# stx_v2.net
KiCad netlist of a schematic drawn in EAGLE
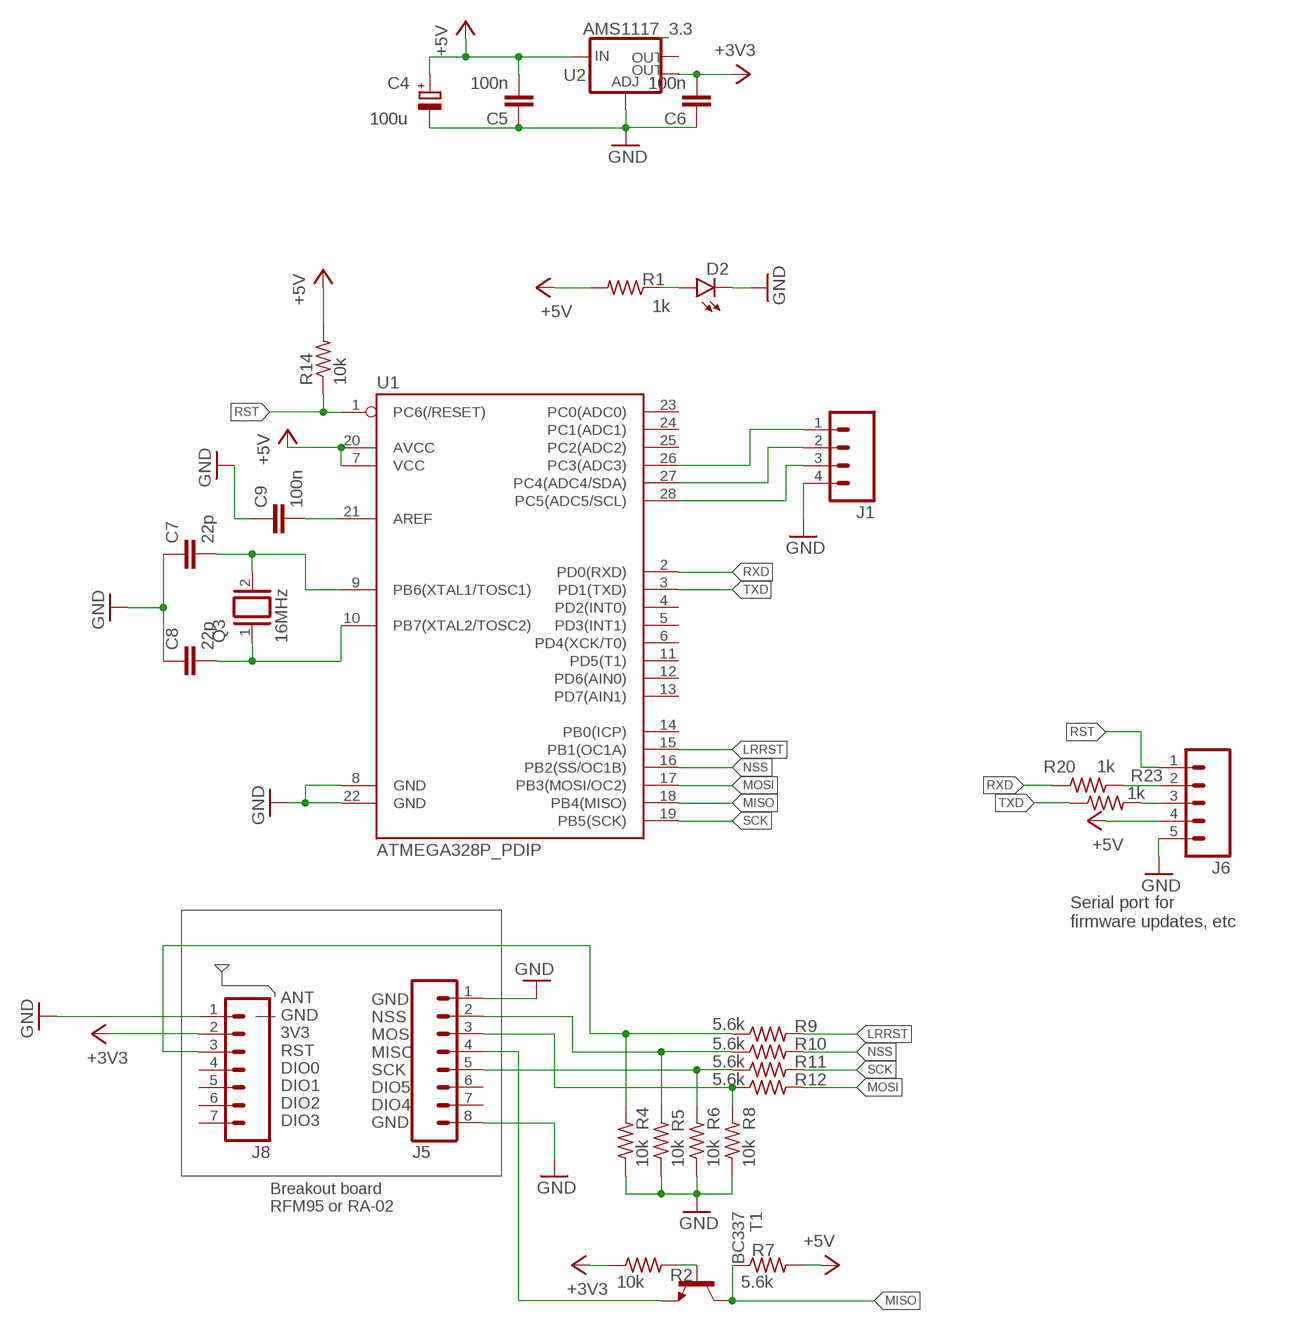
[diagram p0: schematic, sheet 1]

(export (version "E")
  (design (tool "Eeschema 10.0.6"))
  (components
    (comp (ref "C4")
      (value "100u")
      (footprint "eagle-import:E2,5-6E")
      (libsource (lib "eagle-import") (part "CPOL-EUE2,5-6E"))
    )
    (comp (ref "C5")
      (value "100n")
      (footprint "eagle-import:C050-024X044")
      (libsource (lib "eagle-import") (part "C-EU050-024X044"))
    )
    (comp (ref "C6")
      (value "100n")
      (footprint "eagle-import:C050-024X044")
      (libsource (lib "eagle-import") (part "C-EU050-024X044"))
    )
    (comp (ref "C7")
      (value "22p")
      (footprint "eagle-import:C050-024X044")
      (libsource (lib "eagle-import") (part "C-EU050-024X044"))
    )
    (comp (ref "C8")
      (value "22p")
      (footprint "eagle-import:C050-024X044")
      (libsource (lib "eagle-import") (part "C-EU050-024X044"))
    )
    (comp (ref "C9")
      (value "100n")
      (footprint "eagle-import:C050-024X044")
      (libsource (lib "eagle-import") (part "C-EU050-024X044"))
    )
    (comp (ref "D2")
      (value "LED3MM")
      (footprint "eagle-import:LED3MM")
      (libsource (lib "eagle-import") (part "LED3MM"))
    )
    (comp (ref "J1")
      (value "M04PTH")
      (footprint "eagle-import:1X04")
      (libsource (lib "eagle-import") (part "M04PTH"))
    )
    (comp (ref "J5")
      (value "M08")
      (footprint "eagle-import:1X08_ROUND")
      (libsource (lib "eagle-import") (part "M08"))
    )
    (comp (ref "J6")
      (value "M05PTH")
      (footprint "eagle-import:1X05")
      (libsource (lib "eagle-import") (part "M05PTH"))
    )
    (comp (ref "J8")
      (value "M07")
      (footprint "eagle-import:1X07")
      (libsource (lib "eagle-import") (part "M07"))
    )
    (comp (ref "Q3")
      (value "16MHz")
      (footprint "eagle-import:QS")
      (libsource (lib "eagle-import") (part "XTAL/S"))
    )
    (comp (ref "R1")
      (value "1k")
      (footprint "eagle-import:0204V")
      (libsource (lib "eagle-import") (part "R-US_0204/2V"))
    )
    (comp (ref "R2")
      (value "10k")
      (footprint "eagle-import:0204_7")
      (libsource (lib "eagle-import") (part "R-US_0204/7"))
    )
    (comp (ref "R4")
      (value "10k")
      (footprint "eagle-import:0204V")
      (libsource (lib "eagle-import") (part "R-US_0204/2V"))
    )
    (comp (ref "R5")
      (value "10k")
      (footprint "eagle-import:0204V")
      (libsource (lib "eagle-import") (part "R-US_0204/2V"))
    )
    (comp (ref "R6")
      (value "10k")
      (footprint "eagle-import:0204V")
      (libsource (lib "eagle-import") (part "R-US_0204/2V"))
    )
    (comp (ref "R7")
      (value "5.6k")
      (footprint "eagle-import:0204V")
      (libsource (lib "eagle-import") (part "R-US_0204/2V"))
    )
    (comp (ref "R8")
      (value "10k")
      (footprint "eagle-import:0204V")
      (libsource (lib "eagle-import") (part "R-US_0204/2V"))
    )
    (comp (ref "R9")
      (value "5.6k")
      (footprint "eagle-import:0204V")
      (libsource (lib "eagle-import") (part "R-US_0204/2V"))
    )
    (comp (ref "R10")
      (value "5.6k")
      (footprint "eagle-import:0204V")
      (libsource (lib "eagle-import") (part "R-US_0204/2V"))
    )
    (comp (ref "R11")
      (value "5.6k")
      (footprint "eagle-import:0204V")
      (libsource (lib "eagle-import") (part "R-US_0204/2V"))
    )
    (comp (ref "R12")
      (value "5.6k")
      (footprint "eagle-import:0204V")
      (libsource (lib "eagle-import") (part "R-US_0204/2V"))
    )
    (comp (ref "R14")
      (value "10k")
      (footprint "eagle-import:0204_7")
      (libsource (lib "eagle-import") (part "R-US_0204/7"))
    )
    (comp (ref "R20")
      (value "1k")
      (footprint "eagle-import:0204_7")
      (libsource (lib "eagle-import") (part "R-US_0204/7"))
    )
    (comp (ref "R23")
      (value "1k")
      (footprint "eagle-import:0204_7")
      (libsource (lib "eagle-import") (part "R-US_0204/7"))
    )
    (comp (ref "T1")
      (value "BC337")
      (footprint "eagle-import:TO92")
      (libsource (lib "eagle-import") (part "BC337"))
    )
    (comp (ref "U1")
      (value "ATMEGA328P_PDIP")
      (footprint "eagle-import:DIL28-3")
      (libsource (lib "eagle-import") (part "ATMEGA328P_PDIP"))
    )
    (comp (ref "U2")
      (value "AMS1117_3.3")
      (footprint "eagle-import:SOT223")
      (libsource (lib "eagle-import") (part "V_REG_LM1117SOT223"))
    )
  )
  (nets
    (net (code "1") (name "+3V3") (class "Default")
      (node (ref "C6") (pin "2") (pinfunction "2_2") (pintype "passive"))
      (node (ref "J8") (pin "2") (pinfunction "2_2") (pintype "passive"))
      (node (ref "R2") (pin "1") (pinfunction "1_1") (pintype "passive"))
      (node (ref "U2") (pin "4") (pinfunction "OUT_4") (pintype "output"))
    )
    (net (code "2") (name "+5V") (class "Default")
      (node (ref "C4") (pin "+") (pinfunction "+_+") (pintype "passive"))
      (node (ref "C5") (pin "2") (pinfunction "2_2") (pintype "passive"))
      (node (ref "J6") (pin "4") (pinfunction "4_4") (pintype "passive"))
      (node (ref "R1") (pin "2") (pinfunction "2_2") (pintype "passive"))
      (node (ref "R14") (pin "2") (pinfunction "2_2") (pintype "passive"))
      (node (ref "R7") (pin "2") (pinfunction "2_2") (pintype "passive"))
      (node (ref "U1") (pin "20") (pinfunction "AVCC_20") (pintype "bidirectional"))
      (node (ref "U1") (pin "7") (pinfunction "VCC_7") (pintype "bidirectional"))
      (node (ref "U2") (pin "3") (pinfunction "IN_3") (pintype "input"))
    )
    (net (code "3") (name "GND") (class "Default")
      (node (ref "C4") (pin "-") (pinfunction "-_-") (pintype "passive"))
      (node (ref "C5") (pin "1") (pinfunction "1_1") (pintype "passive"))
      (node (ref "C6") (pin "1") (pinfunction "1_1") (pintype "passive"))
      (node (ref "C7") (pin "1") (pinfunction "1_1") (pintype "passive"))
      (node (ref "C8") (pin "1") (pinfunction "1_1") (pintype "passive"))
      (node (ref "C9") (pin "1") (pinfunction "1_1") (pintype "passive"))
      (node (ref "D2") (pin "K") (pinfunction "C_K") (pintype "passive"))
      (node (ref "J1") (pin "4") (pinfunction "4_4") (pintype "passive"))
      (node (ref "J5") (pin "1") (pinfunction "1_1") (pintype "passive"))
      (node (ref "J5") (pin "8") (pinfunction "8_8") (pintype "passive"))
      (node (ref "J6") (pin "5") (pinfunction "5_5") (pintype "passive"))
      (node (ref "J8") (pin "1") (pinfunction "1_1") (pintype "passive"))
      (node (ref "R4") (pin "1") (pinfunction "1_1") (pintype "passive"))
      (node (ref "R5") (pin "1") (pinfunction "1_1") (pintype "passive"))
      (node (ref "R6") (pin "1") (pinfunction "1_1") (pintype "passive"))
      (node (ref "R8") (pin "1") (pinfunction "1_1") (pintype "passive"))
      (node (ref "U1") (pin "22") (pinfunction "GND_22") (pintype "bidirectional"))
      (node (ref "U1") (pin "8") (pinfunction "GND_8") (pintype "bidirectional"))
      (node (ref "U2") (pin "1") (pinfunction "ADJ_1") (pintype "input"))
    )
    (net (code "4") (name "LRRST") (class "Default")
      (node (ref "R9") (pin "2") (pinfunction "2_2") (pintype "passive"))
      (node (ref "U1") (pin "15") (pinfunction "PB1(OC1A)_15") (pintype "bidirectional"))
    )
    (net (code "5") (name "MISO") (class "Default")
      (node (ref "R7") (pin "1") (pinfunction "1_1") (pintype "passive"))
      (node (ref "T1") (pin "3") (pinfunction "C_3") (pintype "passive"))
      (node (ref "U1") (pin "18") (pinfunction "PB4(MISO)_18") (pintype "bidirectional"))
    )
    (net (code "6") (name "MOSI") (class "Default")
      (node (ref "R12") (pin "2") (pinfunction "2_2") (pintype "passive"))
      (node (ref "U1") (pin "17") (pinfunction "PB3(MOSI/OC2)_17") (pintype "bidirectional"))
    )
    (net (code "7") (name "NSS") (class "Default")
      (node (ref "R10") (pin "2") (pinfunction "2_2") (pintype "passive"))
      (node (ref "U1") (pin "16") (pinfunction "PB2(SS/OC1B)_16") (pintype "bidirectional"))
    )
    (net (code "8") (name "Net-(D2-PadA)") (class "Default")
      (node (ref "D2") (pin "A") (pinfunction "A_A") (pintype "passive"))
      (node (ref "R1") (pin "1") (pinfunction "1_1") (pintype "passive"))
    )
    (net (code "9") (name "Net-(J5-Pad2)") (class "Default")
      (node (ref "J5") (pin "2") (pinfunction "2_2") (pintype "passive"))
      (node (ref "R10") (pin "1") (pinfunction "1_1") (pintype "passive"))
      (node (ref "R5") (pin "2") (pinfunction "2_2") (pintype "passive"))
    )
    (net (code "10") (name "Net-(J5-Pad3)") (class "Default")
      (node (ref "J5") (pin "3") (pinfunction "3_3") (pintype "passive"))
      (node (ref "R12") (pin "1") (pinfunction "1_1") (pintype "passive"))
      (node (ref "R8") (pin "2") (pinfunction "2_2") (pintype "passive"))
    )
    (net (code "11") (name "Net-(J5-Pad5)") (class "Default")
      (node (ref "J5") (pin "5") (pinfunction "5_5") (pintype "passive"))
      (node (ref "R11") (pin "1") (pinfunction "1_1") (pintype "passive"))
      (node (ref "R6") (pin "2") (pinfunction "2_2") (pintype "passive"))
    )
    (net (code "12") (name "Net-(J6-Pad2)") (class "Default")
      (node (ref "J6") (pin "2") (pinfunction "2_2") (pintype "passive"))
      (node (ref "R20") (pin "2") (pinfunction "2_2") (pintype "passive"))
    )
    (net (code "13") (name "Net-(J6-Pad3)") (class "Default")
      (node (ref "J6") (pin "3") (pinfunction "3_3") (pintype "passive"))
      (node (ref "R23") (pin "2") (pinfunction "2_2") (pintype "passive"))
    )
    (net (code "14") (name "Net-(J8-Pad3)") (class "Default")
      (node (ref "J8") (pin "3") (pinfunction "3_3") (pintype "passive"))
      (node (ref "R4") (pin "2") (pinfunction "2_2") (pintype "passive"))
      (node (ref "R9") (pin "1") (pinfunction "1_1") (pintype "passive"))
    )
    (net (code "15") (name "Net-(T1-B)") (class "Default")
      (node (ref "R2") (pin "2") (pinfunction "2_2") (pintype "passive"))
      (node (ref "T1") (pin "2") (pinfunction "B_2") (pintype "passive"))
    )
    (net (code "16") (name "Net-(T1-E)") (class "Default")
      (node (ref "J5") (pin "4") (pinfunction "4_4") (pintype "passive"))
      (node (ref "T1") (pin "1") (pinfunction "E_1") (pintype "passive"))
    )
    (net (code "17") (name "Net-(U1-AREF)") (class "Default")
      (node (ref "C9") (pin "2") (pinfunction "2_2") (pintype "passive"))
      (node (ref "U1") (pin "21") (pinfunction "AREF_21") (pintype "bidirectional"))
    )
    (net (code "18") (name "Net-(U1-PB6(XTAL1{slash}TOSC1))") (class "Default")
      (node (ref "C7") (pin "2") (pinfunction "2_2") (pintype "passive"))
      (node (ref "Q3") (pin "2") (pinfunction "2_2") (pintype "passive"))
      (node (ref "U1") (pin "9") (pinfunction "PB6(XTAL1/TOSC1)_9") (pintype "bidirectional"))
    )
    (net (code "19") (name "Net-(U1-PB7(XTAL2{slash}TOSC2))") (class "Default")
      (node (ref "C8") (pin "2") (pinfunction "2_2") (pintype "passive"))
      (node (ref "Q3") (pin "1") (pinfunction "1_1") (pintype "passive"))
      (node (ref "U1") (pin "10") (pinfunction "PB7(XTAL2/TOSC2)_10") (pintype "bidirectional"))
    )
    (net (code "20") (name "Net-(U1-PC3(ADC3))") (class "Default")
      (node (ref "J1") (pin "1") (pinfunction "1_1") (pintype "passive"))
      (node (ref "U1") (pin "26") (pinfunction "PC3(ADC3)_26") (pintype "bidirectional"))
    )
    (net (code "21") (name "Net-(U1-PC4(ADC4{slash}SDA))") (class "Default")
      (node (ref "J1") (pin "2") (pinfunction "2_2") (pintype "passive"))
      (node (ref "U1") (pin "27") (pinfunction "PC4(ADC4/SDA)_27") (pintype "bidirectional"))
    )
    (net (code "22") (name "Net-(U1-PC5(ADC5{slash}SCL))") (class "Default")
      (node (ref "J1") (pin "3") (pinfunction "3_3") (pintype "passive"))
      (node (ref "U1") (pin "28") (pinfunction "PC5(ADC5/SCL)_28") (pintype "bidirectional"))
    )
    (net (code "23") (name "RST") (class "Default")
      (node (ref "J6") (pin "1") (pinfunction "1_1") (pintype "passive"))
      (node (ref "R14") (pin "1") (pinfunction "1_1") (pintype "passive"))
      (node (ref "U1") (pin "1") (pinfunction "PC6(/RESET)_1") (pintype "bidirectional"))
    )
    (net (code "24") (name "RXD") (class "Default")
      (node (ref "R20") (pin "1") (pinfunction "1_1") (pintype "passive"))
      (node (ref "U1") (pin "2") (pinfunction "PD0(RXD)_2") (pintype "bidirectional"))
    )
    (net (code "25") (name "SCK") (class "Default")
      (node (ref "R11") (pin "2") (pinfunction "2_2") (pintype "passive"))
      (node (ref "U1") (pin "19") (pinfunction "PB5(SCK)_19") (pintype "bidirectional"))
    )
    (net (code "26") (name "TXD") (class "Default")
      (node (ref "R23") (pin "1") (pinfunction "1_1") (pintype "passive"))
      (node (ref "U1") (pin "3") (pinfunction "PD1(TXD)_3") (pintype "bidirectional"))
    )
    (net (code "27") (name "unconnected-(J5-Pad6)") (class "Default")
      (node (ref "J5") (pin "6") (pinfunction "6_6") (pintype "passive"))
    )
    (net (code "28") (name "unconnected-(J5-Pad7)") (class "Default")
      (node (ref "J5") (pin "7") (pinfunction "7_7") (pintype "passive"))
    )
    (net (code "29") (name "unconnected-(J8-Pad4)") (class "Default")
      (node (ref "J8") (pin "4") (pinfunction "4_4") (pintype "passive"))
    )
    (net (code "30") (name "unconnected-(J8-Pad5)") (class "Default")
      (node (ref "J8") (pin "5") (pinfunction "5_5") (pintype "passive"))
    )
    (net (code "31") (name "unconnected-(J8-Pad6)") (class "Default")
      (node (ref "J8") (pin "6") (pinfunction "6_6") (pintype "passive"))
    )
    (net (code "32") (name "unconnected-(J8-Pad7)") (class "Default")
      (node (ref "J8") (pin "7") (pinfunction "7_7") (pintype "passive"))
    )
    (net (code "33") (name "unconnected-(U1-PB0(ICP)-Pad14)") (class "Default")
      (node (ref "U1") (pin "14") (pinfunction "PB0(ICP)_14") (pintype "bidirectional"))
    )
    (net (code "34") (name "unconnected-(U1-PC0(ADC0)-Pad23)") (class "Default")
      (node (ref "U1") (pin "23") (pinfunction "PC0(ADC0)_23") (pintype "bidirectional"))
    )
    (net (code "35") (name "unconnected-(U1-PC1(ADC1)-Pad24)") (class "Default")
      (node (ref "U1") (pin "24") (pinfunction "PC1(ADC1)_24") (pintype "bidirectional"))
    )
    (net (code "36") (name "unconnected-(U1-PC2(ADC2)-Pad25)") (class "Default")
      (node (ref "U1") (pin "25") (pinfunction "PC2(ADC2)_25") (pintype "bidirectional"))
    )
    (net (code "37") (name "unconnected-(U1-PD2(INT0)-Pad4)") (class "Default")
      (node (ref "U1") (pin "4") (pinfunction "PD2(INT0)_4") (pintype "bidirectional"))
    )
    (net (code "38") (name "unconnected-(U1-PD3(INT1)-Pad5)") (class "Default")
      (node (ref "U1") (pin "5") (pinfunction "PD3(INT1)_5") (pintype "bidirectional"))
    )
    (net (code "39") (name "unconnected-(U1-PD4(XCK{slash}T0)-Pad6)") (class "Default")
      (node (ref "U1") (pin "6") (pinfunction "PD4(XCK/T0)_6") (pintype "bidirectional"))
    )
    (net (code "40") (name "unconnected-(U1-PD5(T1)-Pad11)") (class "Default")
      (node (ref "U1") (pin "11") (pinfunction "PD5(T1)_11") (pintype "bidirectional"))
    )
    (net (code "41") (name "unconnected-(U1-PD6(AIN0)-Pad12)") (class "Default")
      (node (ref "U1") (pin "12") (pinfunction "PD6(AIN0)_12") (pintype "bidirectional"))
    )
    (net (code "42") (name "unconnected-(U1-PD7(AIN1)-Pad13)") (class "Default")
      (node (ref "U1") (pin "13") (pinfunction "PD7(AIN1)_13") (pintype "bidirectional"))
    )
    (net (code "43") (name "unconnected-(U2-OUT-Pad2)") (class "Default")
      (node (ref "U2") (pin "2") (pinfunction "OUT_2") (pintype "output"))
    )
  )
)
